# GolgiBotV2_02_Esp.net
KiCad netlist of a schematic drawn in Altium Designer
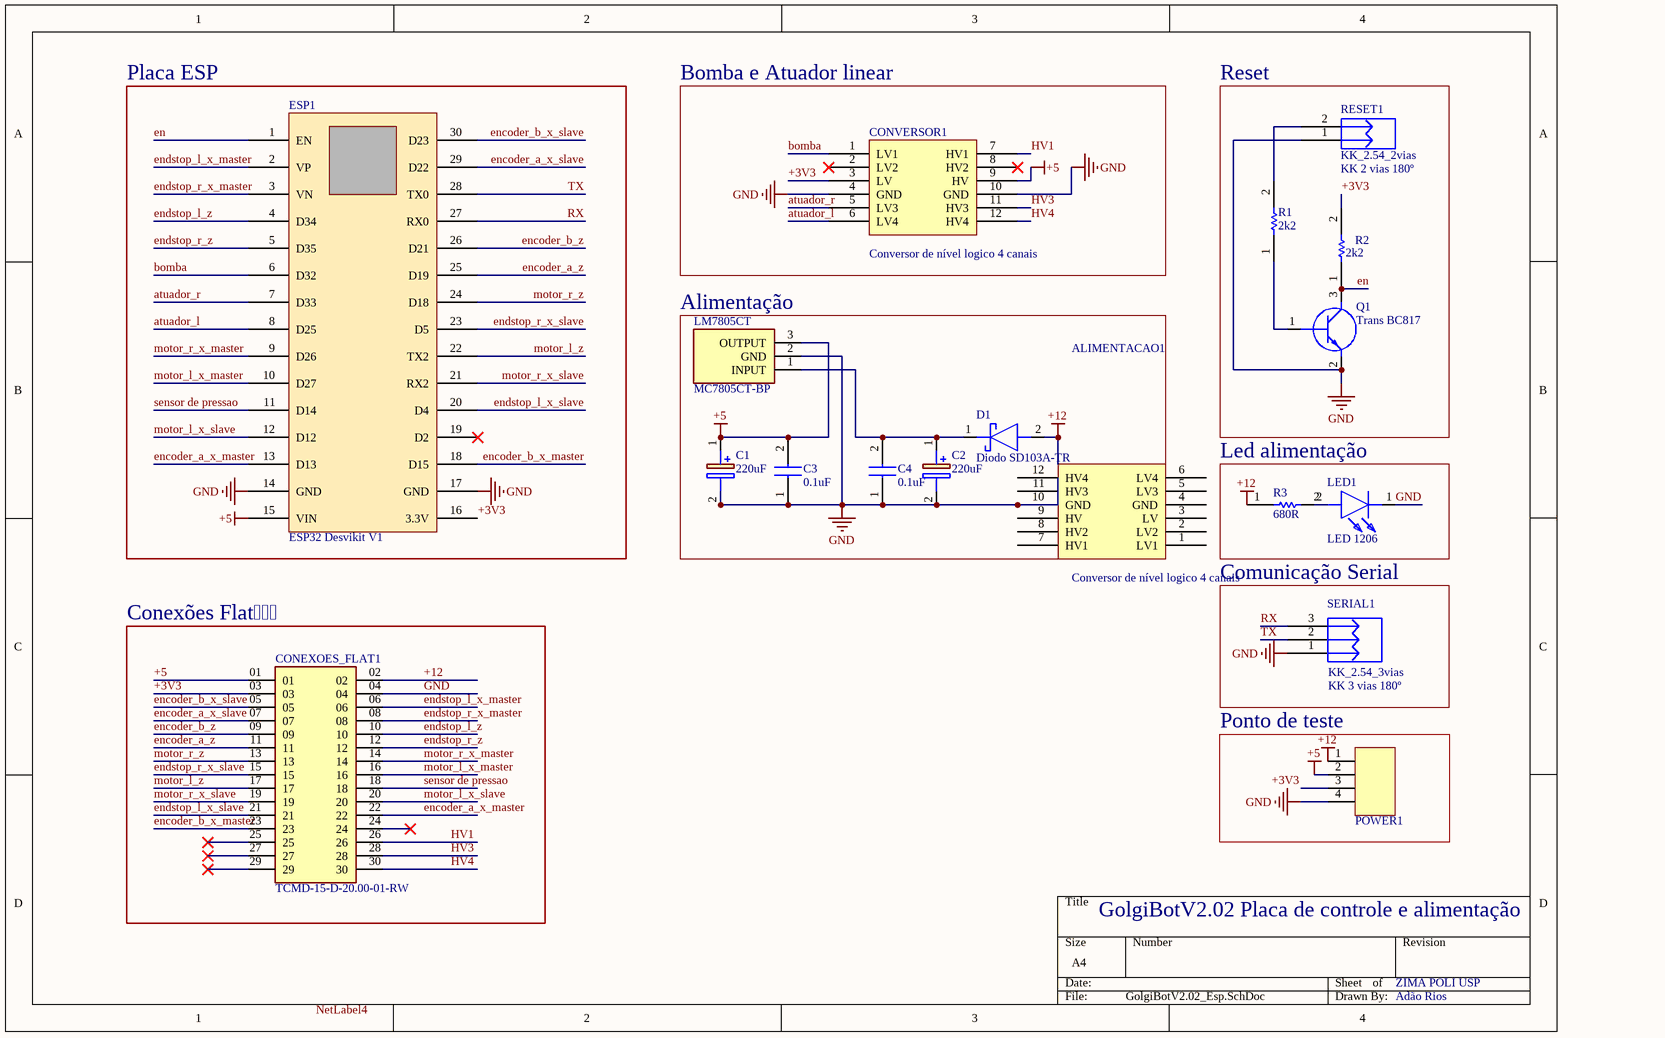
[diagram p0: GolgiBotV2.02_Esp.SchDoc]

(export (version "E")
  (design (tool "Eeschema 10.0.6"))
  (components
    (comp (ref "ALIMENTACAO1")
      (value "Conversor de nível logico 4 canais")
      (footprint "Conversor de nível lógico 4 canais")
      (libsource (lib "golgi_bot_ESP_V2.01") (part "Conversor de nível logico 4 canais"))
    )
    (comp (ref "C1")
      (value "220uF")
      (footprint "CAPPRD200W55D500H1200")
      (description "Capacitor Polarised")
      (fields
        (field (name "MANUFACTURER_PART_NUMBER") "ECA-0JM221")
        (field (name "MOUSER PART NUMBER") "667-ECA-0JM221")
      )
      (libsource (lib "golgi_bot_ESP_V2.01") (part "Capacitor eletrolítico D5mm"))
    )
    (comp (ref "C2")
      (value "220uF")
      (footprint "CAPPRD200W55D500H1200")
      (description "Capacitor Polarised")
      (fields
        (field (name "MANUFACTURER_PART_NUMBER") "ECA-0JM221")
        (field (name "MOUSER PART NUMBER") "667-ECA-0JM221")
      )
      (libsource (lib "golgi_bot_ESP_V2.01") (part "Capacitor eletrolítico D5mm"))
    )
    (comp (ref "C3")
      (value "0.1uF")
      (footprint "CAPC3216X180N")
      (description "Capacitor")
      (fields
        (field (name "MANUFACTURER_PART_NUMBER") "C3216X5R0J226M160AA")
        (field (name "MOUSER PART NUMBER") "810-C3216X5R0J226M-6")
      )
      (libsource (lib "golgi_bot_ESP_V2.01") (part "Capacitor Cerâmico 1206"))
    )
    (comp (ref "C4")
      (value "0.1uF")
      (footprint "CAPC3216X180N")
      (description "Capacitor")
      (fields
        (field (name "MANUFACTURER_PART_NUMBER") "C3216X5R0J226M160AA")
        (field (name "MOUSER PART NUMBER") "810-C3216X5R0J226M-6")
      )
      (libsource (lib "golgi_bot_ESP_V2.01") (part "Capacitor Cerâmico 1206"))
    )
    (comp (ref "CONEXOES_FLAT1")
      (value "TCMD-15-D-20.00-01-RW")
      (footprint "SAMTEC_TCMD-15-D-20.00-01-RW")
      (description "TCMD Series 2.00 mm IDC Ribbon Cable Assembly, Terminal")
      (fields (field (name "MF") "Samtec"))
      (libsource (lib "TCMD-15-D-20.00-01-RW") (part "TCMD-15-D-20.00-01-RW"))
    )
    (comp (ref "CONVERSOR1")
      (value "Conversor de nível logico 4 canais")
      (footprint "Conversor de nível lógico 4 canais")
      (libsource (lib "") (part "Conversor de nível logico 4 canais_1"))
    )
    (comp (ref "D1")
      (value "Diodo SD103A-TR")
      (footprint "DIOAD950W60L350D150")
      (description "Schottky Diode")
      (fields
        (field (name "MANUFACTURER_PART_NUMBER") "SD103A-TR")
        (field (name "MOUSER PART NUMBER") "625-SD103A")
      )
      (libsource (lib "golgi_bot_ESP_V2.01") (part "Diodo SD103A-TR"))
    )
    (comp (ref "ESP1")
      (value "ESP32 Desvikit V1")
      (footprint "ESP32_Desvikit_v1")
      (description "microcontrolador com moculo bluethoth e wifi")
      (fields (field (name "Comment") "microcontrolador"))
      (libsource (lib "golgi_bot_ESP_V2.01") (part "ESP32 Desvikit v1"))
    )
    (comp (ref "LED1")
      (value "LED 1206")
      (footprint "LEDC3214X78N")
      (description "LED")
      (fields
        (field (name "MANUFACTURER_PART_NUMBER") "150120BS75000")
        (field (name "MOUSER PART NUMBER") "710-150120BS75000")
      )
      (libsource (lib "golgi_bot_ESP_V2.01") (part "LED 1206"))
    )
    (comp (ref "LM7805CT")
      (value "MC7805CT-BP")
      (footprint "TO255P460X1020X2008-3P")
      (description "Integrated Circuit")
      (fields (field (name "MOUSER PART NUMBER") "833-MC7805CT-BP"))
      (libsource (lib "golgi_bot_ESP_V2.01") (part "MC7805CT-BP"))
    )
    (comp (ref "POWER1")
      (value "Testing PADS 1x4")
      (footprint "Testing PADS 1x4")
      (description "Headers & Wire Housings 40Pin 2mm Spacing Single Row Hdrs, 5pc")
      (fields (field (name "MANUFACTURER") "Cromax"))
      (libsource (lib "golgi_bot_ESP_V2.01") (part "Testing PADS 1x4"))
    )
    (comp (ref "Q1")
      (value "Trans BC817")
      (footprint "SOT96P240X110-3N")
      (description "Transistor BJT NPN BC817-25-7-F")
      (fields
        (field (name "MANUFACTURER_PART_NUMBER") "BC817-25-7-F")
        (field (name "MOUSER PART NUMBER") "621-BC817-25-7-F")
      )
      (libsource (lib "golgi_bot_ESP_V2.01") (part "Trans BC817"))
    )
    (comp (ref "R1")
      (value "2k2")
      (footprint "RESC3216X60N")
      (fields
        (field (name "MANUFACTURER_PART_NUMBER") "CRCW12064K70FKEA")
        (field (name "MOUSER PART NUMBER") "71-CRCW1206-4.7K-E3")
      )
      (libsource (lib "golgi_bot_ESP_V2.01") (part "Resistor 1206"))
    )
    (comp (ref "R2")
      (value "2k2")
      (footprint "RESC3216X60N")
      (fields
        (field (name "MANUFACTURER_PART_NUMBER") "CRCW12064K70FKEA")
        (field (name "MOUSER PART NUMBER") "71-CRCW1206-4.7K-E3")
      )
      (libsource (lib "golgi_bot_ESP_V2.01") (part "Resistor 1206"))
    )
    (comp (ref "R3")
      (value "680R")
      (footprint "RESC3216X60N")
      (fields
        (field (name "MANUFACTURER_PART_NUMBER") "CRCW12064K70FKEA")
        (field (name "MOUSER PART NUMBER") "71-CRCW1206-4.7K-E3")
      )
      (libsource (lib "golgi_bot_ESP_V2.01") (part "Resistor 1206"))
    )
    (comp (ref "RESET1")
      (value "KK_2.54_2vias")
      (footprint "KK_2VIAS_180º")
      (description "Conector KK 2.54mm 2 vias")
      (fields (field (name "VALOR") "KK 2 vias 180º"))
      (libsource (lib "golgi_bot_ESP_V2.01") (part "KK_2.54_2vias"))
    )
    (comp (ref "SERIAL1")
      (value "KK_2.54_3vias")
      (footprint "KK_3vias_180º")
      (description "Conector KK 2.54mm 3 vias")
      (fields (field (name "VALOR") "KK 3 vias 180º"))
      (libsource (lib "golgi_bot_ESP_V2.01") (part "KK_2.54_3vias"))
    )
  )
  (nets
    (net (code "1") (name "+5") (class "Default")
      (node (ref "C1") (pin "1") (pinfunction "+_1") (pintype "passive"))
      (node (ref "C3") (pin "2") (pinfunction "2_2") (pintype "passive"))
      (node (ref "CONEXOES_FLAT1") (pin "01") (pinfunction "01_01") (pintype "passive"))
      (node (ref "CONVERSOR1") (pin "9") (pinfunction "HV_9") (pintype "passive"))
      (node (ref "ESP1") (pin "15") (pinfunction "VIN_15") (pintype "passive"))
      (node (ref "LM7805CT") (pin "3") (pinfunction "OUTPUT_3") (pintype "passive"))
      (node (ref "POWER1") (pin "2") (pintype "passive"))
    )
    (net (code "2") (name "+12") (class "Default")
      (node (ref "CONEXOES_FLAT1") (pin "02") (pinfunction "02_02") (pintype "passive"))
      (node (ref "D1") (pin "2") (pinfunction "A_2") (pintype "passive"))
      (node (ref "POWER1") (pin "1") (pintype "passive"))
      (node (ref "R3") (pin "1") (pinfunction "1_1") (pintype "passive"))
    )
    (net (code "3") (name "/+3V3") (class "Default")
      (node (ref "CONEXOES_FLAT1") (pin "03") (pinfunction "03_03") (pintype "passive"))
      (node (ref "CONVERSOR1") (pin "3") (pinfunction "LV_3") (pintype "passive"))
      (node (ref "ESP1") (pin "16") (pinfunction "3.3V_16") (pintype "passive"))
      (node (ref "POWER1") (pin "3") (pintype "passive"))
      (node (ref "R2") (pin "2") (pinfunction "2_2") (pintype "passive"))
    )
    (net (code "4") (name "/HV1") (class "Default")
      (node (ref "CONEXOES_FLAT1") (pin "26") (pinfunction "26_26") (pintype "passive"))
      (node (ref "CONVERSOR1") (pin "7") (pinfunction "HV1_7") (pintype "passive"))
    )
    (net (code "5") (name "/HV3") (class "Default")
      (node (ref "CONEXOES_FLAT1") (pin "28") (pinfunction "28_28") (pintype "passive"))
      (node (ref "CONVERSOR1") (pin "11") (pinfunction "HV3_11") (pintype "passive"))
    )
    (net (code "6") (name "/HV4") (class "Default")
      (node (ref "CONEXOES_FLAT1") (pin "30") (pinfunction "30_30") (pintype "passive"))
      (node (ref "CONVERSOR1") (pin "12") (pinfunction "HV4_12") (pintype "passive"))
    )
    (net (code "8") (name "/RX") (class "Default")
      (node (ref "ESP1") (pin "27") (pinfunction "RX0_27") (pintype "passive"))
      (node (ref "SERIAL1") (pin "3") (pintype "passive"))
    )
    (net (code "9") (name "/TX") (class "Default")
      (node (ref "ESP1") (pin "28") (pinfunction "TX0_28") (pintype "passive"))
      (node (ref "SERIAL1") (pin "2") (pintype "passive"))
    )
    (net (code "10") (name "/atuador_l") (class "Default")
      (node (ref "CONVERSOR1") (pin "6") (pinfunction "LV4_6") (pintype "passive"))
      (node (ref "ESP1") (pin "8") (pinfunction "D25_8") (pintype "passive"))
    )
    (net (code "11") (name "/atuador_r") (class "Default")
      (node (ref "CONVERSOR1") (pin "5") (pinfunction "LV3_5") (pintype "passive"))
      (node (ref "ESP1") (pin "7") (pinfunction "D33_7") (pintype "passive"))
    )
    (net (code "12") (name "/bomba") (class "Default")
      (node (ref "CONVERSOR1") (pin "1") (pinfunction "LV1_1") (pintype "passive"))
      (node (ref "ESP1") (pin "6") (pinfunction "D32_6") (pintype "passive"))
    )
    (net (code "13") (name "/en") (class "Default")
      (node (ref "ESP1") (pin "1") (pinfunction "EN_1") (pintype "passive"))
      (node (ref "Q1") (pin "3") (pinfunction "C_3") (pintype "passive"))
      (node (ref "R2") (pin "1") (pinfunction "1_1") (pintype "passive"))
    )
    (net (code "14") (name "/encoder_a_x_master") (class "Default")
      (node (ref "CONEXOES_FLAT1") (pin "22") (pinfunction "22_22") (pintype "passive"))
      (node (ref "ESP1") (pin "13") (pinfunction "D13_13") (pintype "passive"))
    )
    (net (code "15") (name "/encoder_a_x_slave") (class "Default")
      (node (ref "CONEXOES_FLAT1") (pin "07") (pinfunction "07_07") (pintype "passive"))
      (node (ref "ESP1") (pin "29") (pinfunction "D22_29") (pintype "passive"))
    )
    (net (code "16") (name "/encoder_a_z") (class "Default")
      (node (ref "CONEXOES_FLAT1") (pin "11") (pinfunction "11_11") (pintype "passive"))
      (node (ref "ESP1") (pin "25") (pinfunction "D19_25") (pintype "passive"))
    )
    (net (code "17") (name "/encoder_b_x_master") (class "Default")
      (node (ref "CONEXOES_FLAT1") (pin "23") (pinfunction "23_23") (pintype "passive"))
      (node (ref "ESP1") (pin "18") (pinfunction "D15_18") (pintype "passive"))
    )
    (net (code "18") (name "/encoder_b_x_slave") (class "Default")
      (node (ref "CONEXOES_FLAT1") (pin "05") (pinfunction "05_05") (pintype "passive"))
      (node (ref "ESP1") (pin "30") (pinfunction "D23_30") (pintype "passive"))
    )
    (net (code "19") (name "/encoder_b_z") (class "Default")
      (node (ref "CONEXOES_FLAT1") (pin "09") (pinfunction "09_09") (pintype "passive"))
      (node (ref "ESP1") (pin "26") (pinfunction "D21_26") (pintype "passive"))
    )
    (net (code "20") (name "/endstop_l_x_master") (class "Default")
      (node (ref "CONEXOES_FLAT1") (pin "06") (pinfunction "06_06") (pintype "passive"))
      (node (ref "ESP1") (pin "2") (pinfunction "VP_2") (pintype "passive"))
    )
    (net (code "21") (name "/endstop_l_x_slave") (class "Default")
      (node (ref "CONEXOES_FLAT1") (pin "21") (pinfunction "21_21") (pintype "passive"))
      (node (ref "ESP1") (pin "20") (pinfunction "D4_20") (pintype "passive"))
    )
    (net (code "22") (name "/endstop_l_z") (class "Default")
      (node (ref "CONEXOES_FLAT1") (pin "10") (pinfunction "10_10") (pintype "passive"))
      (node (ref "ESP1") (pin "4") (pinfunction "D34_4") (pintype "passive"))
    )
    (net (code "23") (name "/endstop_r_x_master") (class "Default")
      (node (ref "CONEXOES_FLAT1") (pin "08") (pinfunction "08_08") (pintype "passive"))
      (node (ref "ESP1") (pin "3") (pinfunction "VN_3") (pintype "passive"))
    )
    (net (code "24") (name "/endstop_r_x_slave") (class "Default")
      (node (ref "CONEXOES_FLAT1") (pin "15") (pinfunction "15_15") (pintype "passive"))
      (node (ref "ESP1") (pin "23") (pinfunction "D5_23") (pintype "passive"))
    )
    (net (code "25") (name "/endstop_r_z") (class "Default")
      (node (ref "CONEXOES_FLAT1") (pin "12") (pinfunction "12_12") (pintype "passive"))
      (node (ref "ESP1") (pin "5") (pinfunction "D35_5") (pintype "passive"))
    )
    (net (code "26") (name "/motor_l_x_master") (class "Default")
      (node (ref "CONEXOES_FLAT1") (pin "16") (pinfunction "16_16") (pintype "passive"))
      (node (ref "ESP1") (pin "10") (pinfunction "D27_10") (pintype "passive"))
    )
    (net (code "27") (name "/motor_l_x_slave") (class "Default")
      (node (ref "CONEXOES_FLAT1") (pin "20") (pinfunction "20_20") (pintype "passive"))
      (node (ref "ESP1") (pin "12") (pinfunction "D12_12") (pintype "passive"))
    )
    (net (code "28") (name "/motor_l_z") (class "Default")
      (node (ref "CONEXOES_FLAT1") (pin "17") (pinfunction "17_17") (pintype "passive"))
      (node (ref "ESP1") (pin "22") (pinfunction "TX2_22") (pintype "passive"))
    )
    (net (code "29") (name "/motor_r_x_master") (class "Default")
      (node (ref "CONEXOES_FLAT1") (pin "14") (pinfunction "14_14") (pintype "passive"))
      (node (ref "ESP1") (pin "9") (pinfunction "D26_9") (pintype "passive"))
    )
    (net (code "30") (name "/motor_r_x_slave") (class "Default")
      (node (ref "CONEXOES_FLAT1") (pin "19") (pinfunction "19_19") (pintype "passive"))
      (node (ref "ESP1") (pin "21") (pinfunction "RX2_21") (pintype "passive"))
    )
    (net (code "31") (name "/motor_r_z") (class "Default")
      (node (ref "CONEXOES_FLAT1") (pin "13") (pinfunction "13_13") (pintype "passive"))
      (node (ref "ESP1") (pin "24") (pinfunction "D18_24") (pintype "passive"))
    )
    (net (code "32") (name "/sensor de pressao") (class "Default")
      (node (ref "CONEXOES_FLAT1") (pin "18") (pinfunction "18_18") (pintype "passive"))
      (node (ref "ESP1") (pin "11") (pinfunction "D14_11") (pintype "passive"))
    )
    (net (code "33") (name "GND") (class "Default")
      (node (ref "ALIMENTACAO1") (pin "10") (pinfunction "GND_10") (pintype "passive"))
      (node (ref "C1") (pin "2") (pinfunction "-_2") (pintype "passive"))
      (node (ref "C2") (pin "2") (pinfunction "-_2") (pintype "passive"))
      (node (ref "C3") (pin "1") (pinfunction "1_1") (pintype "passive"))
      (node (ref "C4") (pin "1") (pinfunction "1_1") (pintype "passive"))
      (node (ref "CONEXOES_FLAT1") (pin "04") (pinfunction "04_04") (pintype "passive"))
      (node (ref "CONVERSOR1") (pin "10") (pinfunction "GND_10") (pintype "passive"))
      (node (ref "CONVERSOR1") (pin "4") (pinfunction "GND_4") (pintype "passive"))
      (node (ref "ESP1") (pin "14") (pinfunction "GND_14") (pintype "passive"))
      (node (ref "ESP1") (pin "17") (pinfunction "GND_17") (pintype "passive"))
      (node (ref "LED1") (pin "1") (pinfunction "K_1") (pintype "passive"))
      (node (ref "LM7805CT") (pin "2") (pinfunction "GND_2") (pintype "passive"))
      (node (ref "POWER1") (pin "4") (pintype "passive"))
      (node (ref "Q1") (pin "2") (pinfunction "E_2") (pintype "passive"))
      (node (ref "RESET1") (pin "1") (pintype "passive"))
      (node (ref "SERIAL1") (pin "1") (pintype "passive"))
    )
    (net (code "34") (name "Net-(C2-+)") (class "Default")
      (node (ref "C2") (pin "1") (pinfunction "+_1") (pintype "passive"))
      (node (ref "C4") (pin "2") (pinfunction "2_2") (pintype "passive"))
      (node (ref "D1") (pin "1") (pinfunction "K_1") (pintype "passive"))
      (node (ref "LM7805CT") (pin "1") (pinfunction "INPUT_1") (pintype "passive"))
    )
    (net (code "35") (name "Net-(LED1-A)") (class "Default")
      (node (ref "LED1") (pin "2") (pinfunction "A_2") (pintype "passive"))
      (node (ref "R3") (pin "2") (pinfunction "2_2") (pintype "passive"))
    )
    (net (code "36") (name "Net-(Q1-B)") (class "Default")
      (node (ref "Q1") (pin "1") (pinfunction "B_1") (pintype "passive"))
      (node (ref "R1") (pin "1") (pinfunction "1_1") (pintype "passive"))
    )
    (net (code "37") (name "Net-(R1-Pad2)") (class "Default")
      (node (ref "R1") (pin "2") (pinfunction "2_2") (pintype "passive"))
      (node (ref "RESET1") (pin "2") (pintype "passive"))
    )
    (net (code "38") (name "unconnected-(ALIMENTACAO1-GND-Pad4)") (class "Default")
      (node (ref "ALIMENTACAO1") (pin "4") (pinfunction "GND_4") (pintype "passive"))
    )
    (net (code "39") (name "unconnected-(ALIMENTACAO1-HV-Pad9)") (class "Default")
      (node (ref "ALIMENTACAO1") (pin "9") (pinfunction "HV_9") (pintype "passive"))
    )
    (net (code "40") (name "unconnected-(ALIMENTACAO1-HV1-Pad7)") (class "Default")
      (node (ref "ALIMENTACAO1") (pin "7") (pinfunction "HV1_7") (pintype "passive"))
    )
    (net (code "41") (name "unconnected-(ALIMENTACAO1-HV2-Pad8)") (class "Default")
      (node (ref "ALIMENTACAO1") (pin "8") (pinfunction "HV2_8") (pintype "passive"))
    )
    (net (code "42") (name "unconnected-(ALIMENTACAO1-HV3-Pad11)") (class "Default")
      (node (ref "ALIMENTACAO1") (pin "11") (pinfunction "HV3_11") (pintype "passive"))
    )
    (net (code "43") (name "unconnected-(ALIMENTACAO1-HV4-Pad12)") (class "Default")
      (node (ref "ALIMENTACAO1") (pin "12") (pinfunction "HV4_12") (pintype "passive"))
    )
    (net (code "44") (name "unconnected-(ALIMENTACAO1-LV-Pad3)") (class "Default")
      (node (ref "ALIMENTACAO1") (pin "3") (pinfunction "LV_3") (pintype "passive"))
    )
    (net (code "45") (name "unconnected-(ALIMENTACAO1-LV1-Pad1)") (class "Default")
      (node (ref "ALIMENTACAO1") (pin "1") (pinfunction "LV1_1") (pintype "passive"))
    )
    (net (code "46") (name "unconnected-(ALIMENTACAO1-LV2-Pad2)") (class "Default")
      (node (ref "ALIMENTACAO1") (pin "2") (pinfunction "LV2_2") (pintype "passive"))
    )
    (net (code "47") (name "unconnected-(ALIMENTACAO1-LV3-Pad5)") (class "Default")
      (node (ref "ALIMENTACAO1") (pin "5") (pinfunction "LV3_5") (pintype "passive"))
    )
    (net (code "48") (name "unconnected-(ALIMENTACAO1-LV4-Pad6)") (class "Default")
      (node (ref "ALIMENTACAO1") (pin "6") (pinfunction "LV4_6") (pintype "passive"))
    )
    (net (code "49") (name "unconnected-(CONEXOES_FLAT1-Pad24)") (class "Default")
      (node (ref "CONEXOES_FLAT1") (pin "24") (pinfunction "24_24") (pintype "passive+no_connect"))
    )
    (net (code "50") (name "unconnected-(CONEXOES_FLAT1-Pad25)") (class "Default")
      (node (ref "CONEXOES_FLAT1") (pin "25") (pinfunction "25_25") (pintype "passive+no_connect"))
    )
    (net (code "51") (name "unconnected-(CONEXOES_FLAT1-Pad27)") (class "Default")
      (node (ref "CONEXOES_FLAT1") (pin "27") (pinfunction "27_27") (pintype "passive+no_connect"))
    )
    (net (code "52") (name "unconnected-(CONEXOES_FLAT1-Pad29)") (class "Default")
      (node (ref "CONEXOES_FLAT1") (pin "29") (pinfunction "29_29") (pintype "passive+no_connect"))
    )
    (net (code "53") (name "unconnected-(CONVERSOR1-HV2-Pad8)") (class "Default")
      (node (ref "CONVERSOR1") (pin "8") (pinfunction "HV2_8") (pintype "passive+no_connect"))
    )
    (net (code "54") (name "unconnected-(CONVERSOR1-LV2-Pad2)") (class "Default")
      (node (ref "CONVERSOR1") (pin "2") (pinfunction "LV2_2") (pintype "passive+no_connect"))
    )
    (net (code "55") (name "unconnected-(ESP1-D2-Pad19)") (class "Default")
      (node (ref "ESP1") (pin "19") (pinfunction "D2_19") (pintype "passive+no_connect"))
    )
  )
)
